# design.net
KiCad netlist of a schematic drawn in Altium Designer
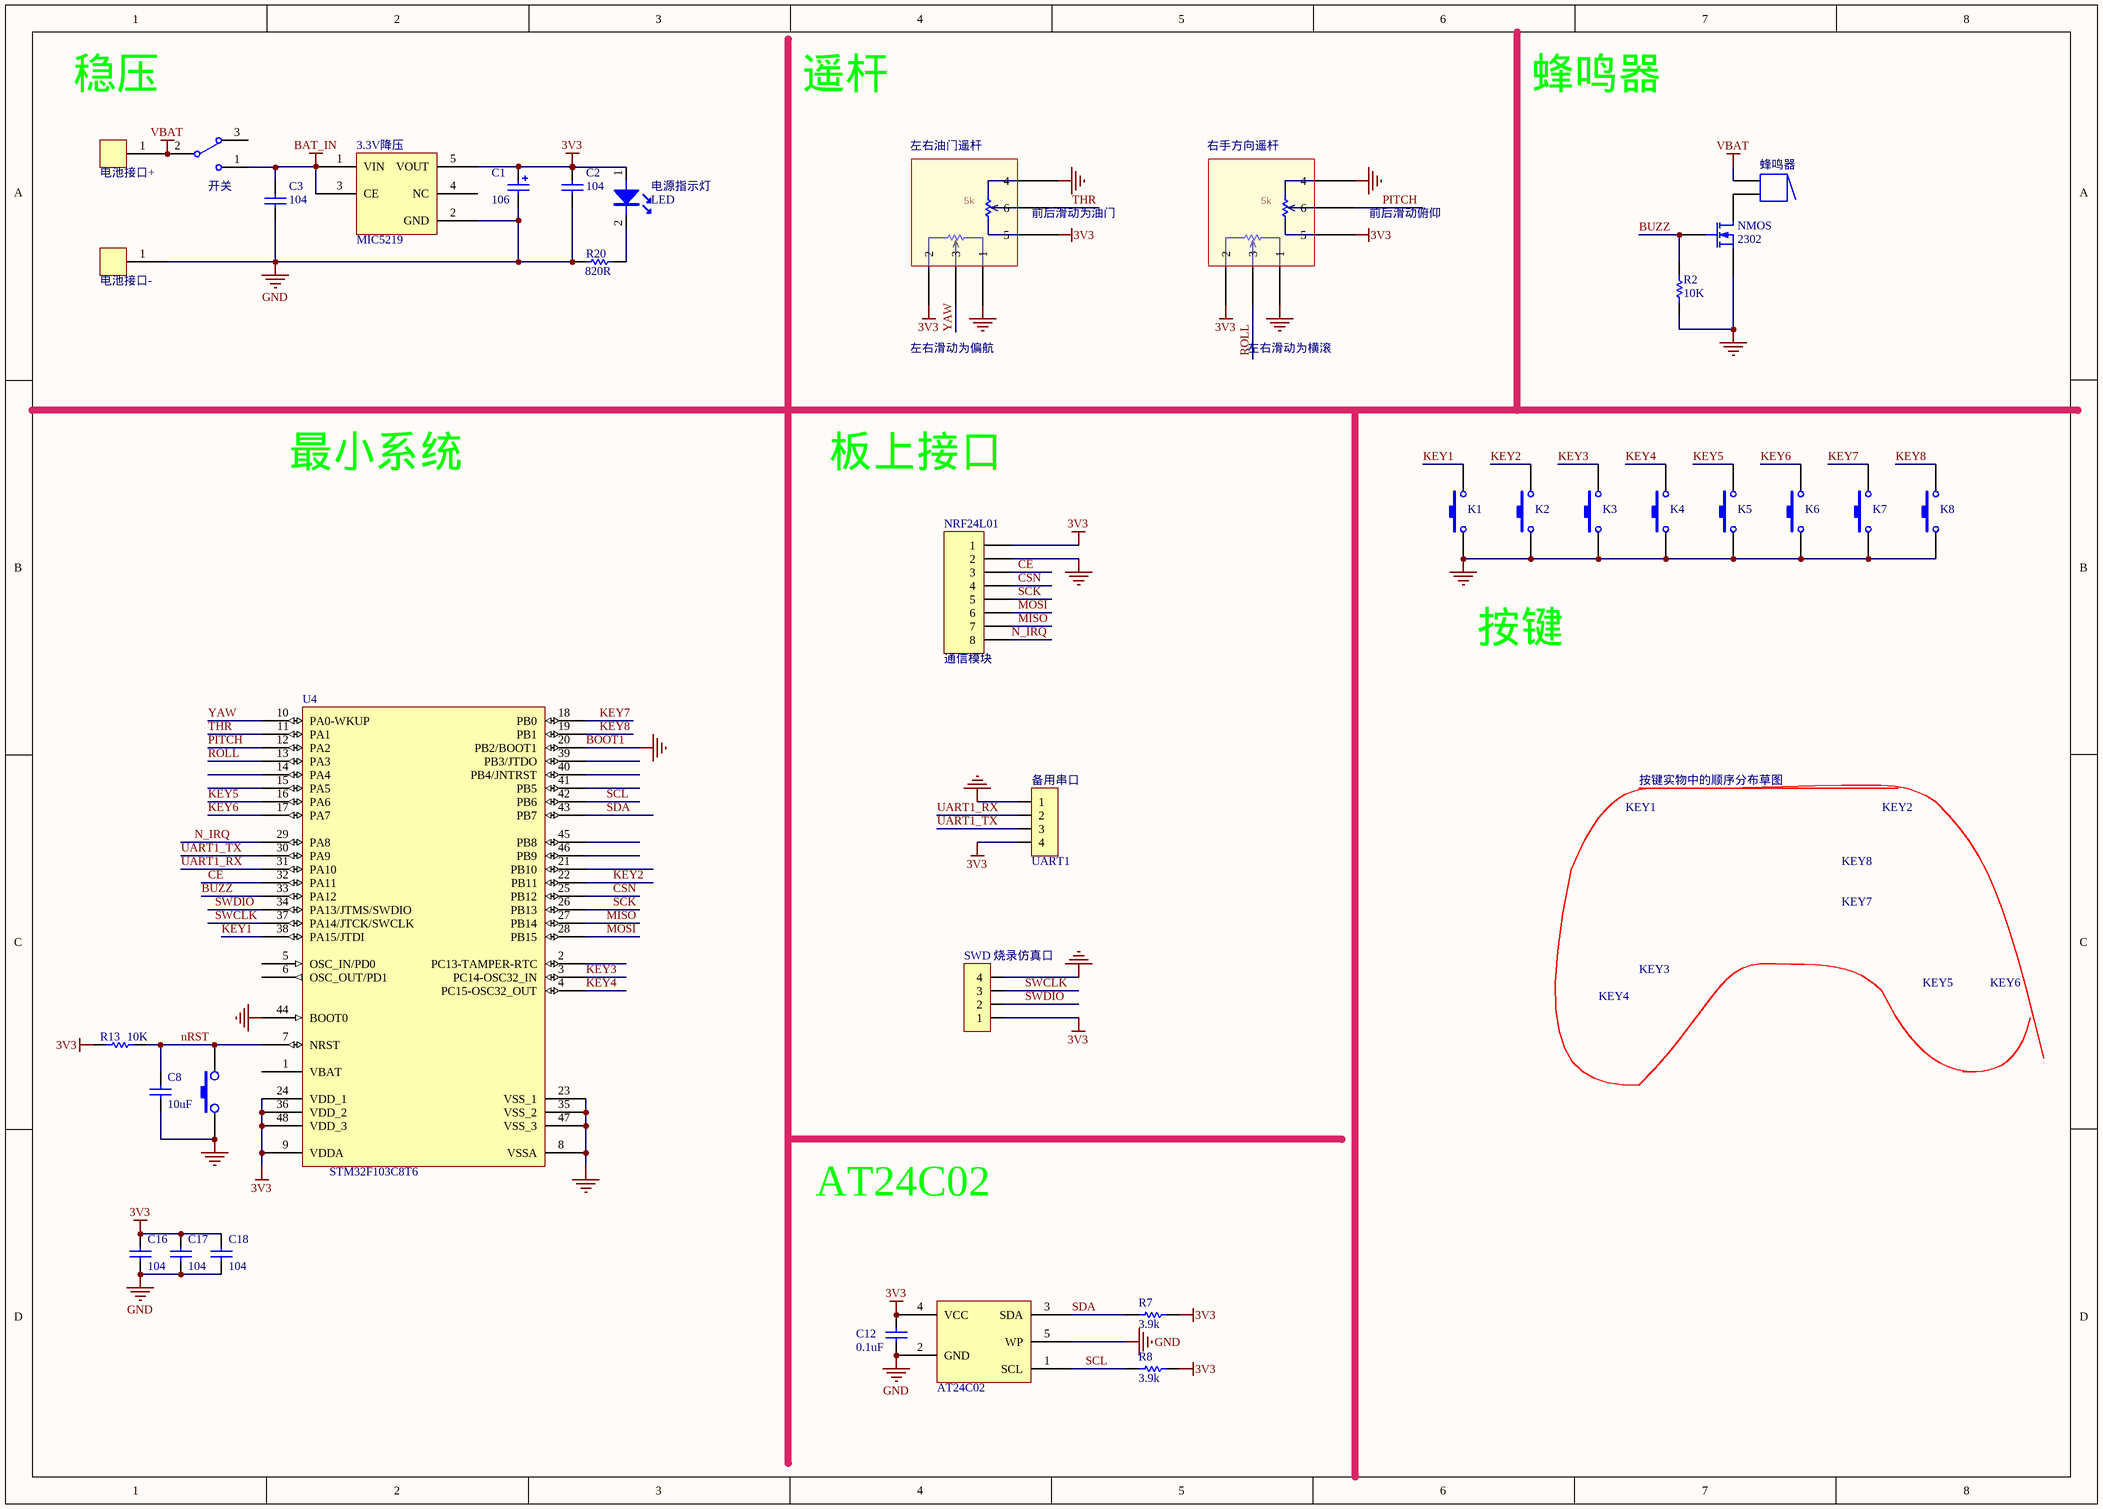
[diagram p0: 遥控原理图.SchDoc]

(export (version "E")
  (design (tool "Eeschema 10.0.6"))
  (components
    (comp (ref "*1") (value "AT24C02") (footprint "SOT23-5") (libsource (lib "开源小遥控") (part "AT24C02")))
    (comp (ref "3.3V降压")
      (value "MIC5219")
      (footprint "SOT23-5")
      (libsource (lib "quadrotor") (part "HT7X33"))
    )
    (comp (ref "C1")
      (value "106")
      (footprint "1206")
      (description "Polarized Capacitor (Radial)")
      (fields
        (field (name "VOLTAGE") "16V")
        (field (name "Comment") "Cap Tan A")
        (field (name "PUBLISHER") "Altium Limited")
      )
      (libsource (lib "ChapuIntegratedLibrary") (part "Cap Tan A"))
    )
    (comp (ref "C2")
      (value "104")
      (footprint "1206_C")
      (description "Polarized Capacitor (Radial)")
      (fields (field (name "Comment") "Cap Chip 1206") (field (name "PUBLISHER") "Altium Limited"))
      (libsource (lib "ChapuIntegratedLibrary") (part "Cap Chip 1206"))
    )
    (comp (ref "C3")
      (value "104")
      (footprint "0603_C")
      (description "Polarized Capacitor (Radial)")
      (fields (field (name "Comment") "Cap Chip 1206") (field (name "PUBLISHER") "Altium Limited"))
      (libsource (lib "ChapuIntegratedLibrary") (part "Cap Chip 1206"))
    )
    (comp (ref "C8") (value "10uF") (footprint "0603_C") (libsource (lib "1218迷你四轴工程_1") (part "C0603")))
    (comp (ref "C12")
      (value "0.1uF")
      (footprint "0603C")
      (description "Capacitor")
      (fields (field (name "Comment") "Cap") (field (name "PUBLISHER") "Altium Limited"))
      (libsource (lib "Miscellaneous Devices") (part "Cap"))
    )
    (comp (ref "C16") (value "104") (footprint "0603_C") (libsource (lib "1218迷你四轴工程_1") (part "C0603")))
    (comp (ref "C17") (value "104") (footprint "0603_C") (libsource (lib "1218迷你四轴工程_1") (part "C0603")))
    (comp (ref "C18") (value "104") (footprint "0603_C") (libsource (lib "1218迷你四轴工程_1") (part "C0603")))
    (comp (ref "K1")
      (value "40%（油門上限）")
      (footprint "4脚贴片点动开关")
      (description "Switch")
      (fields (field (name "PUBLISHER") "Altium Limited"))
      (libsource (lib "Miscellaneous Devices") (part "SW-PB"))
    )
    (comp (ref "K2")
      (value "60%")
      (footprint "4脚贴片点动开关")
      (description "Switch")
      (fields (field (name "PUBLISHER") "Altium Limited"))
      (libsource (lib "Miscellaneous Devices") (part "SW-PB"))
    )
    (comp (ref "K3")
      (value "40%（油門上限）")
      (footprint "4脚贴片点动开关")
      (description "Switch")
      (fields (field (name "PUBLISHER") "Altium Limited"))
      (libsource (lib "Miscellaneous Devices") (part "SW-PB"))
    )
    (comp (ref "K4")
      (value "60%")
      (footprint "4脚贴片点动开关")
      (description "Switch")
      (fields (field (name "PUBLISHER") "Altium Limited"))
      (libsource (lib "Miscellaneous Devices") (part "SW-PB"))
    )
    (comp (ref "K5")
      (value "40%（油門上限）")
      (footprint "4脚贴片点动开关")
      (description "Switch")
      (fields (field (name "PUBLISHER") "Altium Limited"))
      (libsource (lib "Miscellaneous Devices") (part "SW-PB"))
    )
    (comp (ref "K6")
      (value "60%")
      (footprint "4脚贴片点动开关")
      (description "Switch")
      (fields (field (name "PUBLISHER") "Altium Limited"))
      (libsource (lib "Miscellaneous Devices") (part "SW-PB"))
    )
    (comp (ref "K7")
      (value "40%（油門上限）")
      (footprint "4脚贴片点动开关")
      (description "Switch")
      (fields (field (name "PUBLISHER") "Altium Limited"))
      (libsource (lib "Miscellaneous Devices") (part "SW-PB"))
    )
    (comp (ref "K8")
      (value "60%")
      (footprint "4脚贴片点动开关")
      (description "Switch")
      (fields (field (name "PUBLISHER") "Altium Limited"))
      (libsource (lib "Miscellaneous Devices") (part "SW-PB"))
    )
    (comp (ref "NMOS")
      (value "2302")
      (footprint "SOT-23-3")
      (description "N-Channel MOSFET")
      (fields (field (name "PUBLISHER") "Altium Limited"))
      (libsource (lib "Miscellaneous Devices") (part "MOSFET-N"))
    )
    (comp (ref "NRF24L01")
      (value "通信模块")
      (footprint "HDR1X8")
      (description "Header, 8-Pin")
      (fields (field (name "PUBLISHER") "Altium Limited"))
      (libsource (lib "Miscellaneous Connectors") (part "Header 8"))
    )
    (comp (ref "R2")
      (value "10K")
      (footprint "0603_R")
      (description "Resistor")
      (fields (field (name "Comment") "222") (field (name "PUBLISHER") "Altium Limited"))
      (libsource (lib "Miscellaneous Devices") (part "Res1"))
    )
    (comp (ref "R7")
      (value "3.9k")
      (footprint "0603R")
      (description "Resistor")
      (fields (field (name "Comment") "222") (field (name "PUBLISHER") "Altium Limited"))
      (libsource (lib "Miscellaneous Devices") (part "Res1"))
    )
    (comp (ref "R8")
      (value "3.9k")
      (footprint "0603R")
      (description "Resistor")
      (fields (field (name "Comment") "222") (field (name "PUBLISHER") "Altium Limited"))
      (libsource (lib "Miscellaneous Devices") (part "Res1"))
    )
    (comp (ref "R13")
      (value "10K")
      (footprint "0603_R")
      (description "Resistor")
      (fields (field (name "Comment") "Res1") (field (name "PUBLISHER") "Altium Limited"))
      (libsource (lib "Miscellaneous Devices") (part "Res1"))
    )
    (comp (ref "R20")
      (value "820R")
      (footprint "0603_R")
      (description "Resistor")
      (fields (field (name "Comment") "222") (field (name "PUBLISHER") "Altium Limited"))
      (libsource (lib "Miscellaneous Devices") (part "Res1"))
    )
    (comp (ref "REST1") (value "SW-PB") (footprint "SW-2") (libsource (lib "SW开关") (part "SW-PB")))
    (comp (ref "SWD 烧录仿真口")
      (value "SWD")
      (footprint "1.27侧卧表贴")
      (description "Header, 4-Pin, Right Angle")
      (fields (field (name "PUBLISHER") "Altium Limited"))
      (libsource (lib "") (part "Header 4H_1"))
    )
    (comp (ref "U4")
      (value "STM32F103C8T6")
      (footprint "LQFP48")
      (libsource (lib "微型四轴") (part "STM32F103C8T6"))
    )
    (comp (ref "右手方向遥杆") (value "摇杆") (footprint "遥控电位器") (libsource (lib "开源小遥控") (part "摇杆")))
    (comp (ref "备用串口")
      (value "UART1")
      (footprint "1.27侧卧表贴")
      (description "Header, 4-Pin, Right Angle")
      (fields (field (name "PUBLISHER") "Altium Limited"))
      (libsource (lib "linch051") (part "Header 4H"))
    )
    (comp (ref "左右油门遥杆") (value "摇杆") (footprint "遥控电位器") (libsource (lib "开源小遥控") (part "摇杆")))
    (comp (ref "开关")
      (value "SW-SPDT")
      (footprint "SW-5")
      (description "SPDT Subminiature Toggle Switch, Right Angle Mounting, Vertical Actuation")
      (fields (field (name "PUBLISHER") "Altium Limited"))
      (libsource (lib "Miscellaneous Devices") (part "SW-SPDT"))
    )
    (comp (ref "电池接口+") (value "Header 1") (footprint "BAT") (libsource (lib "quadrotor") (part "Header 1")))
    (comp (ref "电池接口-") (value "Header 1") (footprint "BAT") (libsource (lib "quadrotor") (part "Header 1")))
    (comp (ref "电源指示灯") (value "LED") (footprint "0603_LED") (libsource (lib "1218迷你四轴工程_1") (part "LED")))
    (comp (ref "蜂鸣器")
      (value "Buzzer")
      (footprint "蜂鸣器9mm")
      (description "Magnetic Transducer Buzzer")
      (fields (field (name "PUBLISHER") "Altium Limited"))
      (libsource (lib "PCB_Project1") (part "Buzzer"))
    )
  )
  (nets
    (net (code "1") (name "/BUZZ") (class "Default")
      (node (ref "NMOS") (pin "2") (pinfunction "G_2") (pintype "passive"))
      (node (ref "R2") (pin "1") (pinfunction "1_1") (pintype "passive"))
      (node (ref "U4") (pin "33") (pinfunction "PA12_33") (pintype "bidirectional"))
    )
    (net (code "2") (name "/CE") (class "Default")
      (node (ref "NRF24L01") (pin "3") (pinfunction "3_3") (pintype "passive"))
      (node (ref "U4") (pin "32") (pinfunction "PA11_32") (pintype "bidirectional"))
    )
    (net (code "3") (name "/CSN") (class "Default")
      (node (ref "NRF24L01") (pin "4") (pinfunction "4_4") (pintype "passive"))
      (node (ref "U4") (pin "25") (pinfunction "PB12_25") (pintype "bidirectional"))
    )
    (net (code "4") (name "/KEY1") (class "Default")
      (node (ref "K1") (pin "2") (pinfunction "2_2") (pintype "passive"))
      (node (ref "U4") (pin "38") (pinfunction "PA15/JTDI_38") (pintype "bidirectional"))
    )
    (net (code "5") (name "/KEY2") (class "Default")
      (node (ref "K2") (pin "2") (pinfunction "2_2") (pintype "passive"))
      (node (ref "U4") (pin "22") (pinfunction "PB11_22") (pintype "bidirectional"))
    )
    (net (code "6") (name "/KEY3") (class "Default")
      (node (ref "K3") (pin "2") (pinfunction "2_2") (pintype "passive"))
      (node (ref "U4") (pin "3") (pinfunction "PC14-OSC32_IN_3") (pintype "bidirectional"))
    )
    (net (code "7") (name "/KEY4") (class "Default")
      (node (ref "K4") (pin "2") (pinfunction "2_2") (pintype "passive"))
      (node (ref "U4") (pin "4") (pinfunction "PC15-OSC32_OUT_4") (pintype "bidirectional"))
    )
    (net (code "8") (name "/KEY5") (class "Default")
      (node (ref "K5") (pin "2") (pinfunction "2_2") (pintype "passive"))
      (node (ref "U4") (pin "16") (pinfunction "PA6_16") (pintype "bidirectional"))
    )
    (net (code "9") (name "/KEY6") (class "Default")
      (node (ref "K6") (pin "2") (pinfunction "2_2") (pintype "passive"))
      (node (ref "U4") (pin "17") (pinfunction "PA7_17") (pintype "bidirectional"))
    )
    (net (code "10") (name "/KEY7") (class "Default")
      (node (ref "K7") (pin "2") (pinfunction "2_2") (pintype "passive"))
      (node (ref "U4") (pin "18") (pinfunction "PB0_18") (pintype "bidirectional"))
    )
    (net (code "11") (name "/KEY8") (class "Default")
      (node (ref "K8") (pin "2") (pinfunction "2_2") (pintype "passive"))
      (node (ref "U4") (pin "19") (pinfunction "PB1_19") (pintype "bidirectional"))
    )
    (net (code "12") (name "/MISO") (class "Default")
      (node (ref "NRF24L01") (pin "7") (pinfunction "7_7") (pintype "passive"))
      (node (ref "U4") (pin "27") (pinfunction "PB14_27") (pintype "bidirectional"))
    )
    (net (code "13") (name "/MOSI") (class "Default")
      (node (ref "NRF24L01") (pin "6") (pinfunction "6_6") (pintype "passive"))
      (node (ref "U4") (pin "28") (pinfunction "PB15_28") (pintype "bidirectional"))
    )
    (net (code "14") (name "/N_IRQ") (class "Default")
      (node (ref "NRF24L01") (pin "8") (pinfunction "8_8") (pintype "passive"))
      (node (ref "U4") (pin "29") (pinfunction "PA8_29") (pintype "bidirectional"))
    )
    (net (code "15") (name "/PITCH") (class "Default")
      (node (ref "U4") (pin "12") (pinfunction "PA2_12") (pintype "bidirectional"))
      (node (ref "右手方向遥杆") (pin "6") (pinfunction "6_6") (pintype "passive"))
    )
    (net (code "16") (name "/ROLL") (class "Default")
      (node (ref "U4") (pin "13") (pinfunction "PA3_13") (pintype "bidirectional"))
      (node (ref "右手方向遥杆") (pin "3") (pinfunction "3_3") (pintype "passive"))
    )
    (net (code "17") (name "/SCK") (class "Default")
      (node (ref "NRF24L01") (pin "5") (pinfunction "5_5") (pintype "passive"))
      (node (ref "U4") (pin "26") (pinfunction "PB13_26") (pintype "bidirectional"))
    )
    (net (code "18") (name "/SCL") (class "Default")
      (node (ref "*1") (pin "1") (pinfunction "SCL_1") (pintype "passive"))
      (node (ref "R8") (pin "1") (pinfunction "1_1") (pintype "passive"))
      (node (ref "U4") (pin "42") (pinfunction "PB6_42") (pintype "bidirectional"))
    )
    (net (code "19") (name "/SDA") (class "Default")
      (node (ref "*1") (pin "3") (pinfunction "SDA_3") (pintype "passive"))
      (node (ref "R7") (pin "1") (pinfunction "1_1") (pintype "passive"))
      (node (ref "U4") (pin "43") (pinfunction "PB7_43") (pintype "bidirectional"))
    )
    (net (code "20") (name "/SWCLK") (class "Default")
      (node (ref "SWD 烧录仿真口") (pin "3") (pinfunction "3_3") (pintype "passive"))
      (node (ref "U4") (pin "37") (pinfunction "PA14/JTCK/SWCLK_37") (pintype "bidirectional"))
    )
    (net (code "21") (name "/SWDIO") (class "Default")
      (node (ref "SWD 烧录仿真口") (pin "2") (pinfunction "2_2") (pintype "passive"))
      (node (ref "U4") (pin "34") (pinfunction "PA13/JTMS/SWDIO_34") (pintype "bidirectional"))
    )
    (net (code "22") (name "/THR") (class "Default")
      (node (ref "U4") (pin "11") (pinfunction "PA1_11") (pintype "bidirectional"))
      (node (ref "左右油门遥杆") (pin "6") (pinfunction "6_6") (pintype "passive"))
    )
    (net (code "23") (name "/UART1_RX") (class "Default")
      (node (ref "U4") (pin "31") (pinfunction "PA10_31") (pintype "bidirectional"))
      (node (ref "备用串口") (pin "2") (pinfunction "2_2") (pintype "passive"))
    )
    (net (code "24") (name "/UART1_TX") (class "Default")
      (node (ref "U4") (pin "30") (pinfunction "PA9_30") (pintype "bidirectional"))
      (node (ref "备用串口") (pin "3") (pinfunction "3_3") (pintype "passive"))
    )
    (net (code "25") (name "/YAW") (class "Default")
      (node (ref "U4") (pin "10") (pinfunction "PA0-WKUP_10") (pintype "bidirectional"))
      (node (ref "左右油门遥杆") (pin "3") (pinfunction "3_3") (pintype "passive"))
    )
    (net (code "26") (name "/nRST") (class "Default")
      (node (ref "C8") (pin "1") (pinfunction "1_1") (pintype "passive"))
      (node (ref "R13") (pin "1") (pinfunction "1_1") (pintype "passive"))
      (node (ref "REST1") (pin "2") (pinfunction "2_2") (pintype "passive"))
      (node (ref "U4") (pin "7") (pinfunction "NRST_7") (pintype "bidirectional"))
    )
    (net (code "27") (name "3V3") (class "Default")
      (node (ref "*1") (pin "4") (pinfunction "VCC_4") (pintype "passive"))
      (node (ref "3.3V降压") (pin "5") (pinfunction "VOUT_5") (pintype "passive"))
      (node (ref "C1") (pin "2") (pinfunction "1_2") (pintype "passive"))
      (node (ref "C12") (pin "1") (pinfunction "1_1") (pintype "passive"))
      (node (ref "C16") (pin "1") (pinfunction "1_1") (pintype "passive"))
      (node (ref "C17") (pin "1") (pinfunction "1_1") (pintype "passive"))
      (node (ref "C18") (pin "1") (pinfunction "1_1") (pintype "passive"))
      (node (ref "C2") (pin "1") (pinfunction "1_1") (pintype "passive"))
      (node (ref "NRF24L01") (pin "1") (pinfunction "1_1") (pintype "passive"))
      (node (ref "R13") (pin "2") (pinfunction "2_2") (pintype "passive"))
      (node (ref "R7") (pin "2") (pinfunction "2_2") (pintype "passive"))
      (node (ref "R8") (pin "2") (pinfunction "2_2") (pintype "passive"))
      (node (ref "SWD 烧录仿真口") (pin "1") (pinfunction "1_1") (pintype "passive"))
      (node (ref "U4") (pin "24") (pinfunction "VDD_1_24") (pintype "power_in"))
      (node (ref "U4") (pin "36") (pinfunction "VDD_2_36") (pintype "power_in"))
      (node (ref "U4") (pin "48") (pinfunction "VDD_3_48") (pintype "power_in"))
      (node (ref "U4") (pin "9") (pinfunction "VDDA_9") (pintype "power_in"))
      (node (ref "右手方向遥杆") (pin "2") (pinfunction "2_2") (pintype "passive"))
      (node (ref "右手方向遥杆") (pin "5") (pinfunction "5_5") (pintype "passive"))
      (node (ref "备用串口") (pin "4") (pinfunction "4_4") (pintype "passive"))
      (node (ref "左右油门遥杆") (pin "2") (pinfunction "2_2") (pintype "passive"))
      (node (ref "左右油门遥杆") (pin "5") (pinfunction "5_5") (pintype "passive"))
      (node (ref "电源指示灯") (pin "1") (pinfunction "1_1") (pintype "passive"))
    )
    (net (code "28") (name "BAT_IN") (class "Default")
      (node (ref "3.3V降压") (pin "1") (pinfunction "VIN_1") (pintype "passive"))
      (node (ref "3.3V降压") (pin "3") (pinfunction "CE_3") (pintype "passive"))
      (node (ref "C3") (pin "1") (pinfunction "1_1") (pintype "passive"))
      (node (ref "开关") (pin "1") (pinfunction "1_1") (pintype "passive"))
    )
    (net (code "29") (name "GND") (class "Default")
      (node (ref "*1") (pin "2") (pinfunction "GND_2") (pintype "passive"))
      (node (ref "*1") (pin "5") (pinfunction "WP_5") (pintype "passive"))
      (node (ref "3.3V降压") (pin "2") (pinfunction "GND_2") (pintype "passive"))
      (node (ref "C1") (pin "1") (pinfunction "2_1") (pintype "passive"))
      (node (ref "C12") (pin "2") (pinfunction "2_2") (pintype "passive"))
      (node (ref "C16") (pin "2") (pinfunction "2_2") (pintype "passive"))
      (node (ref "C17") (pin "2") (pinfunction "2_2") (pintype "passive"))
      (node (ref "C18") (pin "2") (pinfunction "2_2") (pintype "passive"))
      (node (ref "C2") (pin "2") (pinfunction "2_2") (pintype "passive"))
      (node (ref "C3") (pin "2") (pinfunction "2_2") (pintype "passive"))
      (node (ref "C8") (pin "2") (pinfunction "2_2") (pintype "passive"))
      (node (ref "K1") (pin "1") (pinfunction "1_1") (pintype "passive"))
      (node (ref "K2") (pin "1") (pinfunction "1_1") (pintype "passive"))
      (node (ref "K3") (pin "1") (pinfunction "1_1") (pintype "passive"))
      (node (ref "K4") (pin "1") (pinfunction "1_1") (pintype "passive"))
      (node (ref "K5") (pin "1") (pinfunction "1_1") (pintype "passive"))
      (node (ref "K6") (pin "1") (pinfunction "1_1") (pintype "passive"))
      (node (ref "K7") (pin "1") (pinfunction "1_1") (pintype "passive"))
      (node (ref "K8") (pin "1") (pinfunction "1_1") (pintype "passive"))
      (node (ref "NMOS") (pin "3") (pinfunction "S_3") (pintype "passive"))
      (node (ref "NRF24L01") (pin "2") (pinfunction "2_2") (pintype "passive"))
      (node (ref "R2") (pin "2") (pinfunction "2_2") (pintype "passive"))
      (node (ref "R20") (pin "1") (pinfunction "1_1") (pintype "passive"))
      (node (ref "REST1") (pin "1") (pinfunction "1_1") (pintype "passive"))
      (node (ref "SWD 烧录仿真口") (pin "4") (pinfunction "4_4") (pintype "passive"))
      (node (ref "U4") (pin "20") (pinfunction "PB2/BOOT1_20") (pintype "bidirectional"))
      (node (ref "U4") (pin "23") (pinfunction "VSS_1_23") (pintype "power_in"))
      (node (ref "U4") (pin "35") (pinfunction "VSS_2_35") (pintype "power_in"))
      (node (ref "U4") (pin "44") (pinfunction "BOOT0_44") (pintype "input"))
      (node (ref "U4") (pin "47") (pinfunction "VSS_3_47") (pintype "power_in"))
      (node (ref "U4") (pin "8") (pinfunction "VSSA_8") (pintype "power_in"))
      (node (ref "右手方向遥杆") (pin "1") (pinfunction "1_1") (pintype "passive"))
      (node (ref "右手方向遥杆") (pin "4") (pinfunction "4_4") (pintype "passive"))
      (node (ref "备用串口") (pin "1") (pinfunction "1_1") (pintype "passive"))
      (node (ref "左右油门遥杆") (pin "1") (pinfunction "1_1") (pintype "passive"))
      (node (ref "左右油门遥杆") (pin "4") (pinfunction "4_4") (pintype "passive"))
      (node (ref "电池接口-") (pin "1") (pintype "passive"))
    )
    (net (code "30") (name "Net-(NMOS-D)") (class "Default")
      (node (ref "NMOS") (pin "1") (pinfunction "D_1") (pintype "passive"))
      (node (ref "蜂鸣器") (pin "1") (pinfunction "1_1") (pintype "passive"))
    )
    (net (code "31") (name "Net-(R20-Pad2)") (class "Default")
      (node (ref "R20") (pin "2") (pinfunction "2_2") (pintype "passive"))
      (node (ref "电源指示灯") (pin "2") (pinfunction "2_2") (pintype "passive"))
    )
    (net (code "32") (name "VBAT") (class "Default")
      (node (ref "开关") (pin "2") (pinfunction "2_2") (pintype "passive"))
      (node (ref "电池接口+") (pin "1") (pintype "passive"))
      (node (ref "蜂鸣器") (pin "2") (pinfunction "2_2") (pintype "passive"))
    )
    (net (code "33") (name "unconnected-(3.3V降压-NC-Pad4)") (class "Default")
      (node (ref "3.3V降压") (pin "4") (pinfunction "NC_4") (pintype "passive"))
    )
    (net (code "34") (name "unconnected-(U4-OSC_IN{slash}PD0-Pad5)") (class "Default")
      (node (ref "U4") (pin "5") (pinfunction "OSC_IN/PD0_5") (pintype "input"))
    )
    (net (code "35") (name "unconnected-(U4-OSC_OUT{slash}PD1-Pad6)") (class "Default")
      (node (ref "U4") (pin "6") (pinfunction "OSC_OUT/PD1_6") (pintype "output"))
    )
    (net (code "36") (name "unconnected-(U4-PA4-Pad14)") (class "Default")
      (node (ref "U4") (pin "14") (pinfunction "PA4_14") (pintype "bidirectional"))
    )
    (net (code "37") (name "unconnected-(U4-PA5-Pad15)") (class "Default")
      (node (ref "U4") (pin "15") (pinfunction "PA5_15") (pintype "bidirectional"))
    )
    (net (code "38") (name "unconnected-(U4-PB3{slash}JTDO-Pad39)") (class "Default")
      (node (ref "U4") (pin "39") (pinfunction "PB3/JTDO_39") (pintype "bidirectional"))
    )
    (net (code "39") (name "unconnected-(U4-PB4{slash}JNTRST-Pad40)") (class "Default")
      (node (ref "U4") (pin "40") (pinfunction "PB4/JNTRST_40") (pintype "bidirectional"))
    )
    (net (code "40") (name "unconnected-(U4-PB5-Pad41)") (class "Default")
      (node (ref "U4") (pin "41") (pinfunction "PB5_41") (pintype "bidirectional"))
    )
    (net (code "41") (name "unconnected-(U4-PB8-Pad45)") (class "Default")
      (node (ref "U4") (pin "45") (pinfunction "PB8_45") (pintype "bidirectional"))
    )
    (net (code "42") (name "unconnected-(U4-PB9-Pad46)") (class "Default")
      (node (ref "U4") (pin "46") (pinfunction "PB9_46") (pintype "bidirectional"))
    )
    (net (code "43") (name "unconnected-(U4-PB10-Pad21)") (class "Default")
      (node (ref "U4") (pin "21") (pinfunction "PB10_21") (pintype "bidirectional"))
    )
    (net (code "44") (name "unconnected-(U4-PC13-TAMPER-RTC-Pad2)") (class "Default")
      (node (ref "U4") (pin "2") (pinfunction "PC13-TAMPER-RTC_2") (pintype "bidirectional"))
    )
    (net (code "45") (name "unconnected-(U4-VBAT-Pad1)") (class "Default")
      (node (ref "U4") (pin "1") (pinfunction "VBAT_1") (pintype "power_in"))
    )
    (net (code "46") (name "unconnected-(开关-Pad3)") (class "Default")
      (node (ref "开关") (pin "3") (pinfunction "3_3") (pintype "passive"))
    )
  )
)
